# AFE_MCU.net
KiCad netlist of a schematic drawn in Altium Designer
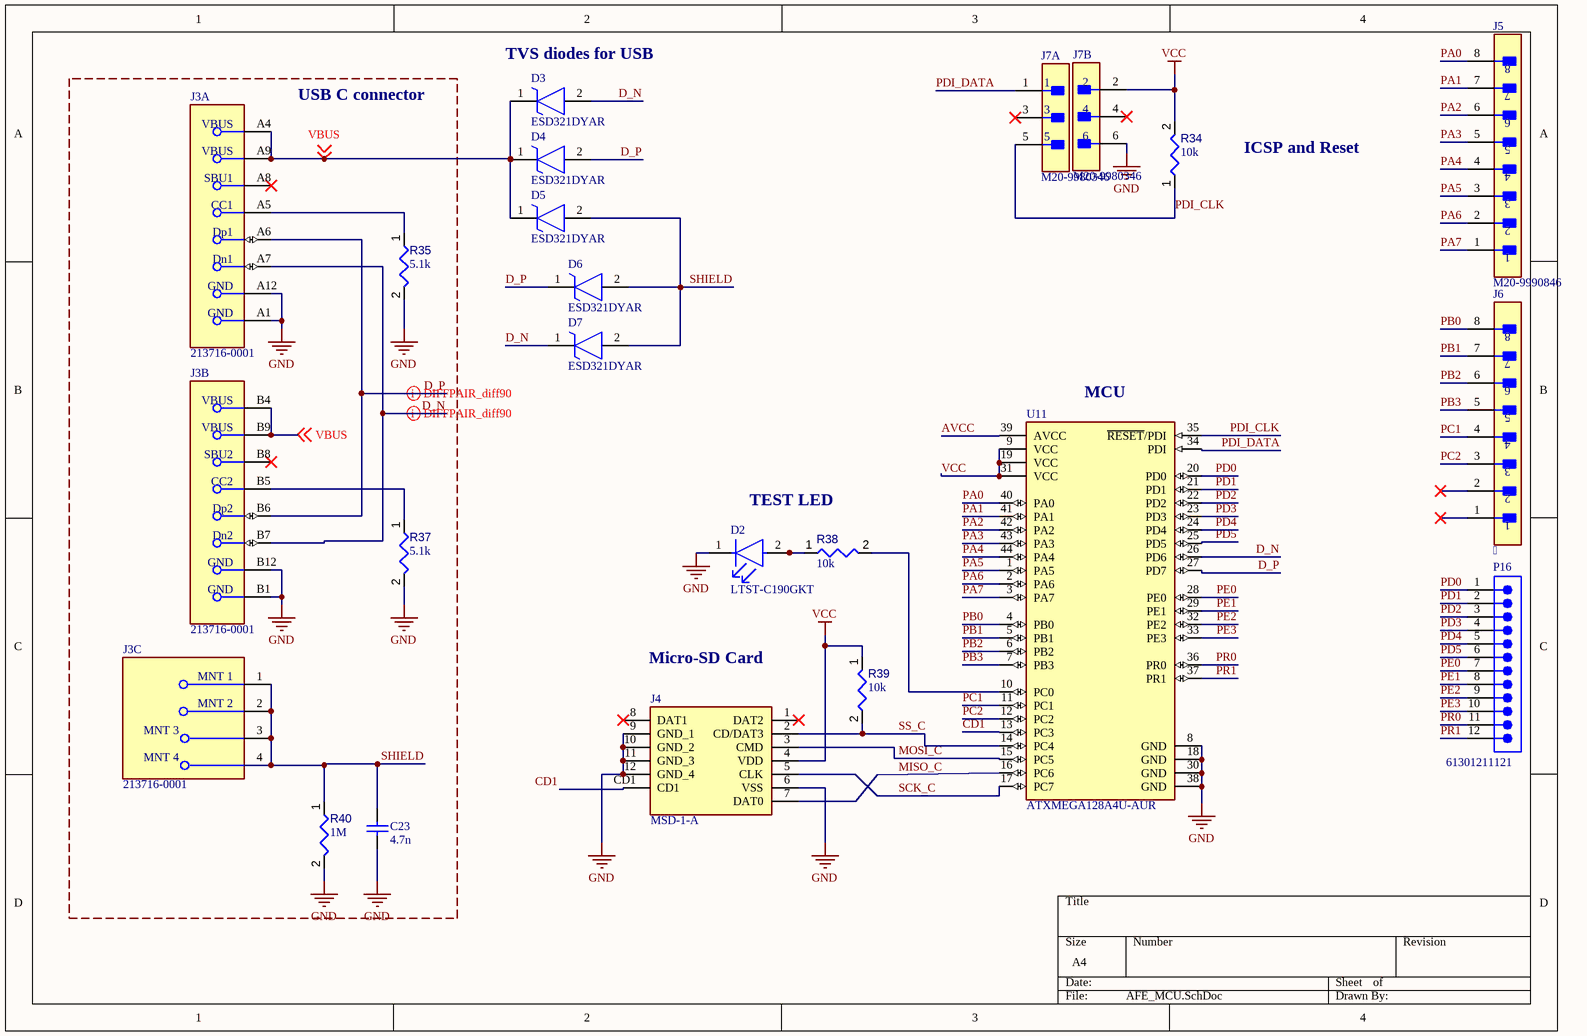
[diagram p0: AFE_MCU.SchDoc]

(export (version "E")
  (design (tool "Eeschema 10.0.6"))
  (components
    (comp (ref "C23")
      (value "4.7n")
      (footprint "WCAP-CSGP_0402_L1W0.5H0.5")
      (description "CAP CER 10000PF 50V X7R 0402")
      (fields (field (name "TOLERANCE") "10%"))
      (libsource (lib "Altium Content Vault") (part "Capacitor_Non-Polarized"))
    )
    (comp (ref "D2")
      (value "LTST-C190GKT")
      (footprint "FP-LTST-C190GKT-MFG")
      (description "LED GREEN CLEAR CHIP SMD")
      (fields (field (name "VOLTAGE") "2V"))
      (libsource (lib "Altium Content Vault") (part "8706943c75ba83719d021d2fdc84c58"))
    )
    (comp (ref "D3")
      (value "ESD321DYAR")
      (footprint "SamacSys:SODFL1608X77N")
      (description "TVS Diode (Uni-directional)")
      (fields (field (name "MOUSER PART NUMBER") "595-ESD321DYAR"))
      (libsource (lib "*") (part "ESD321DYAR"))
    )
    (comp (ref "D4")
      (value "ESD321DYAR")
      (footprint "SamacSys:SODFL1608X77N")
      (description "TVS Diode (Uni-directional)")
      (fields (field (name "MOUSER PART NUMBER") "595-ESD321DYAR"))
      (libsource (lib "*") (part "ESD321DYAR"))
    )
    (comp (ref "D5")
      (value "ESD321DYAR")
      (footprint "SamacSys:SODFL1608X77N")
      (description "TVS Diode (Uni-directional)")
      (fields (field (name "MOUSER PART NUMBER") "595-ESD321DYAR"))
      (libsource (lib "*") (part "ESD321DYAR"))
    )
    (comp (ref "D6")
      (value "ESD321DYAR")
      (footprint "SamacSys:SODFL1608X77N")
      (description "TVS Diode (Uni-directional)")
      (fields (field (name "MOUSER PART NUMBER") "595-ESD321DYAR"))
      (libsource (lib "*") (part "ESD321DYAR"))
    )
    (comp (ref "D7")
      (value "ESD321DYAR")
      (footprint "SamacSys:SODFL1608X77N")
      (description "TVS Diode (Uni-directional)")
      (fields (field (name "MOUSER PART NUMBER") "595-ESD321DYAR"))
      (libsource (lib "*") (part "ESD321DYAR"))
    )
    (comp (ref "J3")
      (value "213716-0001")
      (footprint "FP-213716-0001-MFG")
      (description "CONN RCPT USB2.0 TYPE C 24POS RA")
      (libsource (lib "Altium Content Vault") (part "d371042584e5ad1ff312aac3cd0a0ad"))
    )
    (comp (ref "J4")
      (value "MSD-1-A")
      (footprint "SamacSys:MSD1A")
      (description "Connector")
      (fields (field (name "MOUSER PART NUMBER") "179-MSD-1-A"))
      (libsource (lib "*") (part "MSD-1-A"))
    )
    (comp (ref "J5")
      (value "M20-9990846")
      (footprint "FP-M20-9990846-MFG")
      (description "CONN HEADER VERT 8POS 2.54MM")
      (libsource (lib "Altium Content Vault") (part "99ec2b232beb5d2356d4d77f6a047f0"))
    )
    (comp (ref "J6")
      (value "")
      (footprint "FP-M20-9990846-MFG")
      (description "CONN HEADER VERT 8POS 2.54MM")
      (libsource (lib "Altium Content Vault") (part "99ec2b232beb5d2356d4d77f6a047f0"))
    )
    (comp (ref "J7")
      (value "M20-9980346")
      (footprint "FP-M20-9980346-MFG")
      (description "CONN HEADER VERT 6POS 2.54MM")
      (fields
        (field (name "MANUFACTURER") "Harwin")
        (field (name "OCTOPART") "https://octopart.com/m20-9980346-harwin-5436545")
      )
      (libsource (lib "") (part "2654a11fb13586ecb194516b1c997bc_1"))
    )
    (comp (ref "P16")
      (value "61301211121")
      (footprint "61301211121")
      (libsource (lib "Altium Content Vault") (part "Header_Male_1R_12P"))
    )
    (comp (ref "R34")
      (value "10k")
      (footprint "RESC1005X40X25ML05T05")
      (description "Chip Resistor, 4.7 KOhm, +/- 1%, 63 mW, -55 to 155 degC, 0402 (1005 Metric)")
      (fields (field (name "TOLERANCE") "1%") (field (name "POWER") "63mW"))
      (libsource (lib "Christian Fenger") (part "RES-2"))
    )
    (comp (ref "R35")
      (value "5.1k")
      (footprint "RESC1005X40X25ML05T05")
      (description "Chip Resistor, 4.7 KOhm, +/- 1%, 63 mW, -55 to 155 degC, 0402 (1005 Metric)")
      (fields (field (name "TOLERANCE") "1%") (field (name "POWER") "63mW"))
      (libsource (lib "Christian Fenger") (part "RES-2"))
    )
    (comp (ref "R37")
      (value "5.1k")
      (footprint "RESC1005X40X25ML05T05")
      (description "Chip Resistor, 4.7 KOhm, +/- 1%, 63 mW, -55 to 155 degC, 0402 (1005 Metric)")
      (fields (field (name "TOLERANCE") "1%") (field (name "POWER") "63mW"))
      (libsource (lib "Christian Fenger") (part "RES-2"))
    )
    (comp (ref "R38")
      (value "10k")
      (footprint "RESC1005X40X25ML05T05")
      (description "Chip Resistor, 4.7 KOhm, +/- 1%, 63 mW, -55 to 155 degC, 0402 (1005 Metric)")
      (fields (field (name "TOLERANCE") "1%") (field (name "POWER") "63mW"))
      (libsource (lib "Christian Fenger") (part "RES-2"))
    )
    (comp (ref "R39")
      (value "10k")
      (footprint "RESC1005X40X25ML05T05")
      (description "Chip Resistor, 4.7 KOhm, +/- 1%, 63 mW, -55 to 155 degC, 0402 (1005 Metric)")
      (fields (field (name "TOLERANCE") "1%") (field (name "POWER") "63mW"))
      (libsource (lib "Christian Fenger") (part "RES-2"))
    )
    (comp (ref "R40")
      (value "1M")
      (footprint "RESC1005X40X25ML05T05")
      (description "Chip Resistor, 4.7 KOhm, +/- 1%, 63 mW, -55 to 155 degC, 0402 (1005 Metric)")
      (fields (field (name "TOLERANCE") "1%") (field (name "POWER") "63mW"))
      (libsource (lib "Christian Fenger") (part "RES-2"))
    )
    (comp (ref "U11")
      (value "ATXMEGA128A4U-AUR")
      (footprint "FP-C04-076-IPC_A")
      (description "IC MCU 8/16BIT 128KB FLSH 44TQFP")
      (libsource (lib "Altium Content Vault") (part "9626c523c69d53887b0765d3e361254"))
    )
  )
  (nets
    (net (code "1") (name "/AVCC") (class "Default")
      (node (ref "U11") (pin "39") (pinfunction "AVCC_39") (pintype "power_in"))
    )
    (net (code "2") (name "/CD1") (class "Default")
      (node (ref "J4") (pin "CD1") (pinfunction "CD1_CD1") (pintype "passive"))
      (node (ref "U11") (pin "13") (pinfunction "PC3_13") (pintype "bidirectional"))
    )
    (net (code "3") (name "/D_N") (class "Default")
      (node (ref "D3") (pin "2") (pinfunction "A_2") (pintype "passive"))
      (node (ref "D7") (pin "1") (pinfunction "K_1") (pintype "passive"))
      (node (ref "J3") (pin "A7") (pinfunction "Dn1_A7") (pintype "bidirectional"))
      (node (ref "J3") (pin "B7") (pinfunction "Dn2_B7") (pintype "bidirectional"))
      (node (ref "U11") (pin "26") (pinfunction "PD6_26") (pintype "bidirectional"))
    )
    (net (code "4") (name "/D_P") (class "Default")
      (node (ref "D4") (pin "2") (pinfunction "A_2") (pintype "passive"))
      (node (ref "D6") (pin "1") (pinfunction "K_1") (pintype "passive"))
      (node (ref "J3") (pin "A6") (pinfunction "Dp1_A6") (pintype "bidirectional"))
      (node (ref "J3") (pin "B6") (pinfunction "Dp2_B6") (pintype "bidirectional"))
      (node (ref "U11") (pin "27") (pinfunction "PD7_27") (pintype "bidirectional"))
    )
    (net (code "6") (name "/MISO_C") (class "Default")
      (node (ref "J4") (pin "7") (pinfunction "DAT0_7") (pintype "passive"))
      (node (ref "U11") (pin "16") (pinfunction "PC6_16") (pintype "bidirectional"))
    )
    (net (code "7") (name "/MOSI_C") (class "Default")
      (node (ref "J4") (pin "3") (pinfunction "CMD_3") (pintype "passive"))
      (node (ref "U11") (pin "15") (pinfunction "PC5_15") (pintype "bidirectional"))
    )
    (net (code "8") (name "/PA0") (class "Default")
      (node (ref "J5") (pin "8") (pinfunction "8_8") (pintype "passive"))
      (node (ref "U11") (pin "40") (pinfunction "PA0_40") (pintype "bidirectional"))
    )
    (net (code "9") (name "/PA1") (class "Default")
      (node (ref "J5") (pin "7") (pinfunction "7_7") (pintype "passive"))
      (node (ref "U11") (pin "41") (pinfunction "PA1_41") (pintype "bidirectional"))
    )
    (net (code "10") (name "/PA2") (class "Default")
      (node (ref "J5") (pin "6") (pinfunction "6_6") (pintype "passive"))
      (node (ref "U11") (pin "42") (pinfunction "PA2_42") (pintype "bidirectional"))
    )
    (net (code "11") (name "/PA3") (class "Default")
      (node (ref "J5") (pin "5") (pinfunction "5_5") (pintype "passive"))
      (node (ref "U11") (pin "43") (pinfunction "PA3_43") (pintype "bidirectional"))
    )
    (net (code "12") (name "/PA4") (class "Default")
      (node (ref "J5") (pin "4") (pinfunction "4_4") (pintype "passive"))
      (node (ref "U11") (pin "44") (pinfunction "PA4_44") (pintype "bidirectional"))
    )
    (net (code "13") (name "/PA5") (class "Default")
      (node (ref "J5") (pin "3") (pinfunction "3_3") (pintype "passive"))
      (node (ref "U11") (pin "1") (pinfunction "PA5_1") (pintype "bidirectional"))
    )
    (net (code "14") (name "/PA6") (class "Default")
      (node (ref "J5") (pin "2") (pinfunction "2_2") (pintype "passive"))
      (node (ref "U11") (pin "2") (pinfunction "PA6_2") (pintype "bidirectional"))
    )
    (net (code "15") (name "/PA7") (class "Default")
      (node (ref "J5") (pin "1") (pinfunction "1_1") (pintype "passive"))
      (node (ref "U11") (pin "3") (pinfunction "PA7_3") (pintype "bidirectional"))
    )
    (net (code "16") (name "/PB0") (class "Default")
      (node (ref "J6") (pin "8") (pinfunction "8_8") (pintype "passive"))
      (node (ref "U11") (pin "4") (pinfunction "PB0_4") (pintype "bidirectional"))
    )
    (net (code "17") (name "/PB1") (class "Default")
      (node (ref "J6") (pin "7") (pinfunction "7_7") (pintype "passive"))
      (node (ref "U11") (pin "5") (pinfunction "PB1_5") (pintype "bidirectional"))
    )
    (net (code "18") (name "/PB2") (class "Default")
      (node (ref "J6") (pin "6") (pinfunction "6_6") (pintype "passive"))
      (node (ref "U11") (pin "6") (pinfunction "PB2_6") (pintype "bidirectional"))
    )
    (net (code "19") (name "/PB3") (class "Default")
      (node (ref "J6") (pin "5") (pinfunction "5_5") (pintype "passive"))
      (node (ref "U11") (pin "7") (pinfunction "PB3_7") (pintype "bidirectional"))
    )
    (net (code "20") (name "/PC1") (class "Default")
      (node (ref "J6") (pin "4") (pinfunction "4_4") (pintype "passive"))
      (node (ref "U11") (pin "11") (pinfunction "PC1_11") (pintype "bidirectional"))
    )
    (net (code "21") (name "/PC2") (class "Default")
      (node (ref "J6") (pin "3") (pinfunction "3_3") (pintype "passive"))
      (node (ref "U11") (pin "12") (pinfunction "PC2_12") (pintype "bidirectional"))
    )
    (net (code "22") (name "/PD0") (class "Default")
      (node (ref "P16") (pin "1") (pinfunction "1_1") (pintype "passive"))
      (node (ref "U11") (pin "20") (pinfunction "PD0_20") (pintype "bidirectional"))
    )
    (net (code "23") (name "/PD1") (class "Default")
      (node (ref "P16") (pin "2") (pinfunction "2_2") (pintype "passive"))
      (node (ref "U11") (pin "21") (pinfunction "PD1_21") (pintype "bidirectional"))
    )
    (net (code "24") (name "/PD2") (class "Default")
      (node (ref "P16") (pin "3") (pinfunction "3_3") (pintype "passive"))
      (node (ref "U11") (pin "22") (pinfunction "PD2_22") (pintype "bidirectional"))
    )
    (net (code "25") (name "/PD3") (class "Default")
      (node (ref "P16") (pin "4") (pinfunction "4_4") (pintype "passive"))
      (node (ref "U11") (pin "23") (pinfunction "PD3_23") (pintype "bidirectional"))
    )
    (net (code "26") (name "/PD4") (class "Default")
      (node (ref "P16") (pin "5") (pinfunction "5_5") (pintype "passive"))
      (node (ref "U11") (pin "24") (pinfunction "PD4_24") (pintype "bidirectional"))
    )
    (net (code "27") (name "/PD5") (class "Default")
      (node (ref "P16") (pin "6") (pinfunction "6_6") (pintype "passive"))
      (node (ref "U11") (pin "25") (pinfunction "PD5_25") (pintype "bidirectional"))
    )
    (net (code "28") (name "/PDI_CLK") (class "Default")
      (node (ref "J7") (pin "5") (pinfunction "5_5") (pintype "passive"))
      (node (ref "R34") (pin "1") (pinfunction "1_1") (pintype "passive"))
      (node (ref "U11") (pin "35") (pinfunction "~{RESET}/PDI_35") (pintype "input"))
    )
    (net (code "29") (name "/PDI_DATA") (class "Default")
      (node (ref "J7") (pin "1") (pinfunction "1_1") (pintype "passive"))
      (node (ref "U11") (pin "34") (pinfunction "PDI_34") (pintype "input"))
    )
    (net (code "30") (name "/PE0") (class "Default")
      (node (ref "P16") (pin "7") (pinfunction "7_7") (pintype "passive"))
      (node (ref "U11") (pin "28") (pinfunction "PE0_28") (pintype "bidirectional"))
    )
    (net (code "31") (name "/PE1") (class "Default")
      (node (ref "P16") (pin "8") (pinfunction "8_8") (pintype "passive"))
      (node (ref "U11") (pin "29") (pinfunction "PE1_29") (pintype "bidirectional"))
    )
    (net (code "32") (name "/PE2") (class "Default")
      (node (ref "P16") (pin "9") (pinfunction "9_9") (pintype "passive"))
      (node (ref "U11") (pin "32") (pinfunction "PE2_32") (pintype "bidirectional"))
    )
    (net (code "33") (name "/PE3") (class "Default")
      (node (ref "P16") (pin "10") (pinfunction "10_10") (pintype "passive"))
      (node (ref "U11") (pin "33") (pinfunction "PE3_33") (pintype "bidirectional"))
    )
    (net (code "34") (name "/PR0") (class "Default")
      (node (ref "P16") (pin "11") (pinfunction "11_11") (pintype "passive"))
      (node (ref "U11") (pin "36") (pinfunction "PR0_36") (pintype "bidirectional"))
    )
    (net (code "35") (name "/PR1") (class "Default")
      (node (ref "P16") (pin "12") (pinfunction "12_12") (pintype "passive"))
      (node (ref "U11") (pin "37") (pinfunction "PR1_37") (pintype "bidirectional"))
    )
    (net (code "36") (name "/SCK_C") (class "Default")
      (node (ref "J4") (pin "5") (pinfunction "CLK_5") (pintype "passive"))
      (node (ref "U11") (pin "17") (pinfunction "PC7_17") (pintype "bidirectional"))
    )
    (net (code "37") (name "/SHIELD") (class "Default")
      (node (ref "C23") (pin "2") (pinfunction "2_2") (pintype "passive"))
      (node (ref "D5") (pin "2") (pinfunction "A_2") (pintype "passive"))
      (node (ref "D6") (pin "2") (pinfunction "A_2") (pintype "passive"))
      (node (ref "D7") (pin "2") (pinfunction "A_2") (pintype "passive"))
      (node (ref "J3") (pin "1") (pinfunction "MNT_1_1") (pintype "passive"))
      (node (ref "J3") (pin "2") (pinfunction "MNT_2_2") (pintype "passive"))
      (node (ref "J3") (pin "3") (pinfunction "MNT_3_3") (pintype "passive"))
      (node (ref "J3") (pin "4") (pinfunction "MNT_4_4") (pintype "passive"))
      (node (ref "R40") (pin "1") (pinfunction "1_1") (pintype "passive"))
    )
    (net (code "38") (name "/SS_C") (class "Default")
      (node (ref "J4") (pin "2") (pinfunction "CD/DAT3_2") (pintype "passive"))
      (node (ref "R39") (pin "2") (pinfunction "2_2") (pintype "passive"))
      (node (ref "U11") (pin "14") (pinfunction "PC4_14") (pintype "bidirectional"))
    )
    (net (code "39") (name "GND") (class "Default")
      (node (ref "C23") (pin "1") (pinfunction "1_1") (pintype "passive"))
      (node (ref "D2") (pin "1") (pinfunction "C_1") (pintype "passive"))
      (node (ref "J3") (pin "A1") (pinfunction "GND_A1") (pintype "power_in"))
      (node (ref "J3") (pin "A12") (pinfunction "GND_A12") (pintype "power_in"))
      (node (ref "J3") (pin "B1") (pinfunction "GND_B1") (pintype "power_in"))
      (node (ref "J3") (pin "B12") (pinfunction "GND_B12") (pintype "power_in"))
      (node (ref "J4") (pin "10") (pinfunction "GND_2_10") (pintype "passive"))
      (node (ref "J4") (pin "11") (pinfunction "GND_3_11") (pintype "passive"))
      (node (ref "J4") (pin "12") (pinfunction "GND_4_12") (pintype "passive"))
      (node (ref "J4") (pin "6") (pinfunction "VSS_6") (pintype "passive"))
      (node (ref "J4") (pin "9") (pinfunction "GND_1_9") (pintype "passive"))
      (node (ref "J7") (pin "6") (pinfunction "6_6") (pintype "passive"))
      (node (ref "R35") (pin "2") (pinfunction "2_2") (pintype "passive"))
      (node (ref "R37") (pin "2") (pinfunction "2_2") (pintype "passive"))
      (node (ref "R40") (pin "2") (pinfunction "2_2") (pintype "passive"))
      (node (ref "U11") (pin "18") (pinfunction "GND_18") (pintype "power_in"))
      (node (ref "U11") (pin "30") (pinfunction "GND_30") (pintype "power_in"))
      (node (ref "U11") (pin "38") (pinfunction "GND_38") (pintype "power_in"))
      (node (ref "U11") (pin "8") (pinfunction "GND_8") (pintype "power_in"))
    )
    (net (code "40") (name "Net-(D2-A)") (class "Default")
      (node (ref "D2") (pin "2") (pinfunction "A_2") (pintype "passive"))
      (node (ref "R38") (pin "1") (pinfunction "1_1") (pintype "passive"))
    )
    (net (code "41") (name "Net-(J3A-CC1)") (class "Default")
      (node (ref "J3") (pin "A5") (pinfunction "CC1_A5") (pintype "passive"))
      (node (ref "R35") (pin "1") (pinfunction "1_1") (pintype "passive"))
    )
    (net (code "42") (name "Net-(J3B-CC2)") (class "Default")
      (node (ref "J3") (pin "B5") (pinfunction "CC2_B5") (pintype "passive"))
      (node (ref "R37") (pin "1") (pinfunction "1_1") (pintype "passive"))
    )
    (net (code "43") (name "Net-(U11-PC0)") (class "Default")
      (node (ref "R38") (pin "2") (pinfunction "2_2") (pintype "passive"))
      (node (ref "U11") (pin "10") (pinfunction "PC0_10") (pintype "bidirectional"))
    )
    (net (code "44") (name "VBUS") (class "Default")
      (node (ref "D3") (pin "1") (pinfunction "K_1") (pintype "passive"))
      (node (ref "D4") (pin "1") (pinfunction "K_1") (pintype "passive"))
      (node (ref "D5") (pin "1") (pinfunction "K_1") (pintype "passive"))
      (node (ref "J3") (pin "A4") (pinfunction "VBUS_A4") (pintype "power_in"))
      (node (ref "J3") (pin "A9") (pinfunction "VBUS_A9") (pintype "power_in"))
      (node (ref "J3") (pin "B4") (pinfunction "VBUS_B4") (pintype "power_in"))
      (node (ref "J3") (pin "B9") (pinfunction "VBUS_B9") (pintype "power_in"))
    )
    (net (code "45") (name "VCC") (class "Default")
      (node (ref "J4") (pin "4") (pinfunction "VDD_4") (pintype "passive"))
      (node (ref "J7") (pin "2") (pinfunction "2_2") (pintype "passive"))
      (node (ref "R34") (pin "2") (pinfunction "2_2") (pintype "passive"))
      (node (ref "R39") (pin "1") (pinfunction "1_1") (pintype "passive"))
      (node (ref "U11") (pin "19") (pinfunction "VCC_19") (pintype "power_in"))
      (node (ref "U11") (pin "31") (pinfunction "VCC_31") (pintype "power_in"))
      (node (ref "U11") (pin "9") (pinfunction "VCC_9") (pintype "power_in"))
    )
    (net (code "46") (name "unconnected-(J3A-SBU1-PadA8)") (class "Default")
      (node (ref "J3") (pin "A8") (pinfunction "SBU1_A8") (pintype "passive+no_connect"))
    )
    (net (code "47") (name "unconnected-(J3B-SBU2-PadB8)") (class "Default")
      (node (ref "J3") (pin "B8") (pinfunction "SBU2_B8") (pintype "passive+no_connect"))
    )
    (net (code "48") (name "unconnected-(J4-DAT1-Pad8)") (class "Default")
      (node (ref "J4") (pin "8") (pinfunction "DAT1_8") (pintype "passive+no_connect"))
    )
    (net (code "49") (name "unconnected-(J4-DAT2-Pad1)") (class "Default")
      (node (ref "J4") (pin "1") (pinfunction "DAT2_1") (pintype "passive+no_connect"))
    )
    (net (code "50") (name "unconnected-(J6-Pad1)") (class "Default")
      (node (ref "J6") (pin "1") (pinfunction "1_1") (pintype "passive+no_connect"))
    )
    (net (code "51") (name "unconnected-(J6-Pad2)") (class "Default")
      (node (ref "J6") (pin "2") (pinfunction "2_2") (pintype "passive+no_connect"))
    )
    (net (code "52") (name "unconnected-(J7-Pad3)") (class "Default")
      (node (ref "J7") (pin "3") (pinfunction "3_3") (pintype "passive+no_connect"))
    )
    (net (code "53") (name "unconnected-(J7-Pad4)") (class "Default")
      (node (ref "J7") (pin "4") (pinfunction "4_4") (pintype "passive+no_connect"))
    )
  )
)
